# LTC7818.net
KiCad netlist of a schematic drawn in Altium Designer
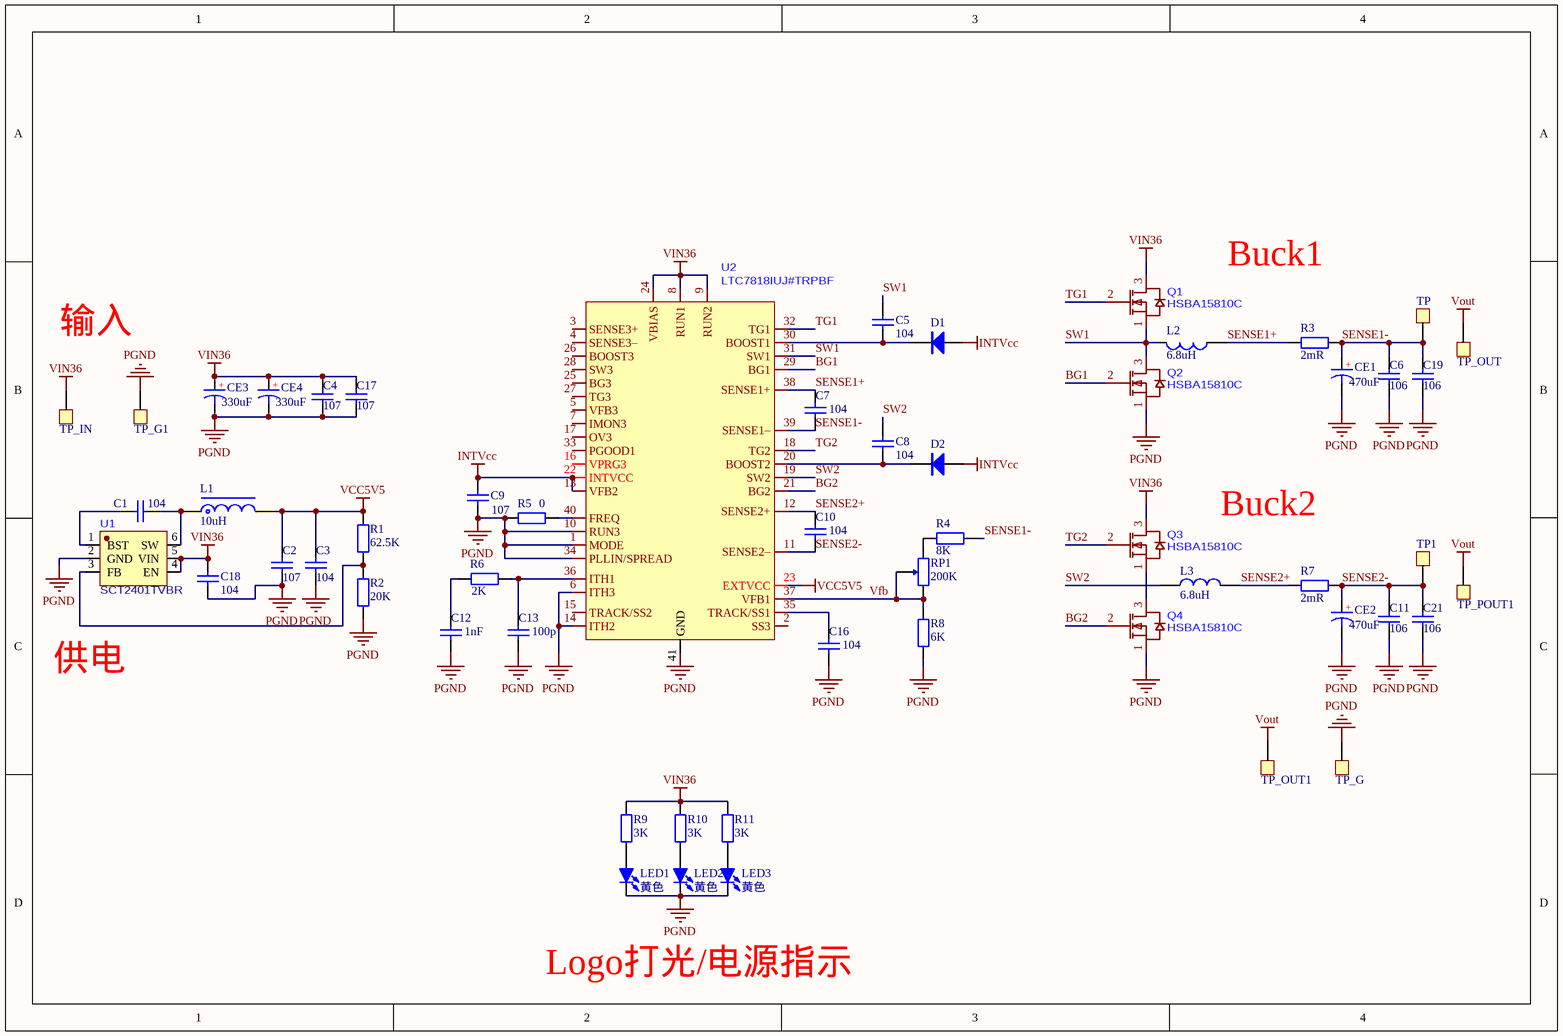
[diagram p0: LTC7818.SchDoc]

(export (version "E")
  (design (tool "Eeschema 10.0.6"))
  (components
    (comp (ref "C1")
      (value "104")
      (footprint "C0603_M")
      (description "贴片电容")
      (libsource (lib "0.1 - 电阻-电容-电感-电位器") (part "C"))
    )
    (comp (ref "C2")
      (value "107")
      (footprint "C0603_M")
      (description "贴片电容")
      (libsource (lib "0.1 - 电阻-电容-电感-电位器") (part "C"))
    )
    (comp (ref "C3")
      (value "104")
      (footprint "C0402_M")
      (description "贴片电容")
      (libsource (lib "0.1 - 电阻-电容-电感-电位器") (part "C"))
    )
    (comp (ref "C4")
      (value "107")
      (footprint "C1210_M")
      (description "贴片电容")
      (libsource (lib "0.1 - 电阻-电容-电感-电位器") (part "C"))
    )
    (comp (ref "C5")
      (value "104")
      (footprint "C0402_M")
      (description "贴片电容")
      (libsource (lib "0.1 - 电阻-电容-电感-电位器") (part "C"))
    )
    (comp (ref "C6")
      (value "106")
      (footprint "C1210_M")
      (description "贴片电容")
      (libsource (lib "0.1 - 电阻-电容-电感-电位器") (part "C"))
    )
    (comp (ref "C7")
      (value "104")
      (footprint "C0402_M")
      (description "贴片电容")
      (libsource (lib "0.1 - 电阻-电容-电感-电位器") (part "C"))
    )
    (comp (ref "C8")
      (value "104")
      (footprint "C0402_M")
      (description "贴片电容")
      (libsource (lib "0.1 - 电阻-电容-电感-电位器") (part "C"))
    )
    (comp (ref "C9")
      (value "107")
      (footprint "C0603_M")
      (description "贴片电容")
      (libsource (lib "0.1 - 电阻-电容-电感-电位器") (part "C"))
    )
    (comp (ref "C10")
      (value "104")
      (footprint "C0402_M")
      (description "贴片电容")
      (libsource (lib "0.1 - 电阻-电容-电感-电位器") (part "C"))
    )
    (comp (ref "C11")
      (value "106")
      (footprint "C1210_M")
      (description "贴片电容")
      (libsource (lib "0.1 - 电阻-电容-电感-电位器") (part "C"))
    )
    (comp (ref "C12")
      (value "1nF")
      (footprint "C0603_M")
      (description "贴片电容")
      (libsource (lib "0.1 - 电阻-电容-电感-电位器") (part "C"))
    )
    (comp (ref "C13")
      (value "100p")
      (footprint "C0603_M")
      (description "贴片电容")
      (libsource (lib "0.1 - 电阻-电容-电感-电位器") (part "C"))
    )
    (comp (ref "C16")
      (value "104")
      (footprint "C0402_M")
      (description "贴片电容")
      (libsource (lib "0.1 - 电阻-电容-电感-电位器") (part "C"))
    )
    (comp (ref "C17")
      (value "107")
      (footprint "C1210_M")
      (description "贴片电容")
      (libsource (lib "0.1 - 电阻-电容-电感-电位器") (part "C"))
    )
    (comp (ref "C18")
      (value "104")
      (footprint "C0603_M")
      (description "贴片电容")
      (libsource (lib "0.1 - 电阻-电容-电感-电位器") (part "C"))
    )
    (comp (ref "C19")
      (value "106")
      (footprint "C1210_M")
      (description "贴片电容")
      (libsource (lib "0.1 - 电阻-电容-电感-电位器") (part "C"))
    )
    (comp (ref "C21")
      (value "106")
      (footprint "C1210_M")
      (description "贴片电容")
      (libsource (lib "0.1 - 电阻-电容-电感-电位器") (part "C"))
    )
    (comp (ref "CE1")
      (value "470uF")
      (footprint "CAP 5.0*10*12.5")
      (description "直插电解电容")
      (libsource (lib "0.1 - 电阻-电容-电感-电位器") (part "CE"))
    )
    (comp (ref "CE2")
      (value "470uF")
      (footprint "CAP 5.0*10*12.5")
      (description "直插电解电容")
      (libsource (lib "0.1 - 电阻-电容-电感-电位器") (part "CE"))
    )
    (comp (ref "CE3")
      (value "330uF")
      (footprint "CAP 5.0*10*12.5")
      (description "直插电解电容")
      (libsource (lib "0.1 - 电阻-电容-电感-电位器") (part "CE"))
    )
    (comp (ref "CE4")
      (value "330uF")
      (footprint "CAP 5.0*10*12.5")
      (description "直插电解电容")
      (libsource (lib "0.1 - 电阻-电容-电感-电位器") (part "CE"))
    )
    (comp (ref "D1")
      (value "~")
      (footprint "SOD-323")
      (description "开关二极管")
      (libsource (lib "0.2 - 二极管-TVS-整流桥") (part "1N4148"))
    )
    (comp (ref "D2")
      (value "~")
      (footprint "SOD-323")
      (description "开关二极管")
      (libsource (lib "0.2 - 二极管-TVS-整流桥") (part "1N4148"))
    )
    (comp (ref "L1")
      (value "10uH")
      (footprint "L-SMD-0630")
      (description "一体成型电感")
      (libsource (lib "0.1 - 电阻-电容-电感-电位器") (part "L-Molding Choke"))
    )
    (comp (ref "L2") (value "6.8uH") (footprint "L_ SER2900") (libsource (lib "LTC7818") (part "L_ SER2900")))
    (comp (ref "L3") (value "6.8uH") (footprint "L_ SER2900") (libsource (lib "LTC7818") (part "L_ SER2900")))
    (comp (ref "LED1")
      (value "黄色")
      (footprint "LED0603_R")
      (description "贴片LED")
      (libsource (lib "0.3 - LED发光二极管") (part "LED-SMD"))
    )
    (comp (ref "LED2")
      (value "黄色")
      (footprint "LED0603_R")
      (description "贴片LED")
      (libsource (lib "0.3 - LED发光二极管") (part "LED-SMD"))
    )
    (comp (ref "LED3")
      (value "黄色")
      (footprint "LED0603_R")
      (description "贴片LED")
      (libsource (lib "0.3 - LED发光二极管") (part "LED-SMD"))
    )
    (comp (ref "Q1")
      (value "HSBA15810C")
      (footprint "PQFN-8_L6.0-W5.0-P1.27-LS6.0-BL")
      (libsource (lib "LTC7818") (part "HSBA15810C"))
    )
    (comp (ref "Q2")
      (value "HSBA15810C")
      (footprint "PQFN-8_L6.0-W5.0-P1.27-LS6.0-BL")
      (libsource (lib "LTC7818") (part "HSBA15810C"))
    )
    (comp (ref "Q3")
      (value "HSBA15810C")
      (footprint "PQFN-8_L6.0-W5.0-P1.27-LS6.0-BL")
      (libsource (lib "LTC7818") (part "HSBA15810C"))
    )
    (comp (ref "Q4")
      (value "HSBA15810C")
      (footprint "PQFN-8_L6.0-W5.0-P1.27-LS6.0-BL")
      (libsource (lib "LTC7818") (part "HSBA15810C"))
    )
    (comp (ref "R1")
      (value "62.5K")
      (footprint "R0603_M")
      (description "贴片电阻")
      (libsource (lib "0.1 - 电阻-电容-电感-电位器") (part "R"))
    )
    (comp (ref "R2")
      (value "20K")
      (footprint "R0603_M")
      (description "贴片电阻")
      (libsource (lib "0.1 - 电阻-电容-电感-电位器") (part "R"))
    )
    (comp (ref "R3")
      (value "2mR")
      (footprint "R2512_M")
      (description "贴片电阻")
      (libsource (lib "0.1 - 电阻-电容-电感-电位器") (part "R"))
    )
    (comp (ref "R4")
      (value "8K")
      (footprint "R0603_M")
      (description "贴片电阻")
      (libsource (lib "0.1 - 电阻-电容-电感-电位器") (part "R"))
    )
    (comp (ref "R5")
      (value "0")
      (footprint "R0603_M")
      (description "贴片电阻")
      (libsource (lib "0.1 - 电阻-电容-电感-电位器") (part "R"))
    )
    (comp (ref "R6")
      (value "2K")
      (footprint "R0603_M")
      (description "贴片电阻")
      (libsource (lib "0.1 - 电阻-电容-电感-电位器") (part "R"))
    )
    (comp (ref "R7")
      (value "2mR")
      (footprint "R2512_M")
      (description "贴片电阻")
      (libsource (lib "0.1 - 电阻-电容-电感-电位器") (part "R"))
    )
    (comp (ref "R8")
      (value "6K")
      (footprint "R0603_M")
      (description "贴片电阻")
      (libsource (lib "0.1 - 电阻-电容-电感-电位器") (part "R"))
    )
    (comp (ref "R9")
      (value "3K")
      (footprint "R0603_M")
      (description "贴片电阻")
      (libsource (lib "0.1 - 电阻-电容-电感-电位器") (part "R"))
    )
    (comp (ref "R10")
      (value "3K")
      (footprint "R0603_M")
      (description "贴片电阻")
      (libsource (lib "0.1 - 电阻-电容-电感-电位器") (part "R"))
    )
    (comp (ref "R11")
      (value "3K")
      (footprint "R0603_M")
      (description "贴片电阻")
      (libsource (lib "0.1 - 电阻-电容-电感-电位器") (part "R"))
    )
    (comp (ref "RP1")
      (value "200K")
      (footprint "3296W")
      (description "单联电位器")
      (libsource (lib "0.1 - 电阻-电容-电感-电位器") (part "RP"))
    )
    (comp (ref "TP") (value "TP") (footprint "CONN-TH_T44001") (libsource (lib "") (part "TP_1")))
    (comp (ref "TP1") (value "TP") (footprint "CONN-TH_T44001") (libsource (lib "") (part "TP_1")))
    (comp (ref "TP_G") (value "TP") (footprint "CONN-TH_T44001") (libsource (lib "LTC7818") (part "TP")))
    (comp (ref "TP_G1") (value "TP") (footprint "CONN-TH_T44001") (libsource (lib "LTC7818") (part "TP")))
    (comp (ref "TP_IN") (value "TP") (footprint "CONN-TH_T44001") (libsource (lib "LTC7818") (part "TP")))
    (comp (ref "TP_OUT") (value "TP") (footprint "CONN-TH_T44001") (libsource (lib "LTC7818") (part "TP")))
    (comp (ref "TP_OUT1") (value "TP") (footprint "CONN-TH_T44001") (libsource (lib "LTC7818") (part "TP")))
    (comp (ref "TP_POUT1") (value "TP") (footprint "CONN-TH_T44001") (libsource (lib "LTC7818") (part "TP")))
    (comp (ref "U1")
      (value "SCT2401TVBR")
      (footprint "SOT23-6M")
      (libsource (lib "主控板") (part "SCT2401TVBR"))
    )
    (comp (ref "U2")
      (value "LTC7818IUJ#TRPBF")
      (footprint "QFN40 6X6_M")
      (libsource (lib "LTC7818") (part "LTC7818IUJ#TRPBF"))
    )
  )
  (nets
    (net (code "1") (name "/BG1") (class "Default")
      (node (ref "Q2") (pin "2") (pinfunction "G_2") (pintype "passive"))
      (node (ref "U2") (pin "29") (pinfunction "BG1_29") (pintype "passive"))
    )
    (net (code "2") (name "/BG2") (class "Default")
      (node (ref "Q4") (pin "2") (pinfunction "G_2") (pintype "passive"))
      (node (ref "U2") (pin "21") (pinfunction "BG2_21") (pintype "passive"))
    )
    (net (code "3") (name "/SENSE1+") (class "Default")
      (node (ref "C7") (pin "1") (pinfunction "1_1") (pintype "passive"))
      (node (ref "L2") (pin "1") (pintype "power_in"))
      (node (ref "R3") (pin "1") (pinfunction "1_1") (pintype "passive"))
      (node (ref "U2") (pin "38") (pinfunction "SENSE1+_38") (pintype "passive"))
    )
    (net (code "4") (name "/SENSE1-") (class "Default")
      (node (ref "C19") (pin "2") (pinfunction "2_2") (pintype "passive"))
      (node (ref "C6") (pin "2") (pinfunction "2_2") (pintype "passive"))
      (node (ref "C7") (pin "2") (pinfunction "2_2") (pintype "passive"))
      (node (ref "CE1") (pin "1") (pinfunction "1_1") (pintype "passive"))
      (node (ref "R3") (pin "2") (pinfunction "2_2") (pintype "passive"))
      (node (ref "R4") (pin "2") (pinfunction "2_2") (pintype "passive"))
      (node (ref "TP") (pin "1") (pinfunction "1_1") (pintype "power_in"))
      (node (ref "U2") (pin "39") (pinfunction "SENSE1–_39") (pintype "passive"))
    )
    (net (code "5") (name "/SENSE2+") (class "Default")
      (node (ref "C10") (pin "1") (pinfunction "1_1") (pintype "passive"))
      (node (ref "L3") (pin "2") (pintype "power_in"))
      (node (ref "R7") (pin "1") (pinfunction "1_1") (pintype "passive"))
      (node (ref "U2") (pin "12") (pinfunction "SENSE2+_12") (pintype "passive"))
    )
    (net (code "6") (name "/SENSE2-") (class "Default")
      (node (ref "C10") (pin "2") (pinfunction "2_2") (pintype "passive"))
      (node (ref "C11") (pin "2") (pinfunction "2_2") (pintype "passive"))
      (node (ref "C21") (pin "2") (pinfunction "2_2") (pintype "passive"))
      (node (ref "CE2") (pin "1") (pinfunction "1_1") (pintype "passive"))
      (node (ref "R7") (pin "2") (pinfunction "2_2") (pintype "passive"))
      (node (ref "TP1") (pin "1") (pinfunction "1_1") (pintype "power_in"))
      (node (ref "U2") (pin "11") (pinfunction "SENSE2–_11") (pintype "passive"))
    )
    (net (code "7") (name "/SW1") (class "Default")
      (node (ref "C5") (pin "1") (pinfunction "1_1") (pintype "passive"))
      (node (ref "L2") (pin "2") (pintype "power_in"))
      (node (ref "Q1") (pin "1") (pinfunction "S_1") (pintype "passive"))
      (node (ref "Q2") (pin "3") (pinfunction "D_3") (pintype "passive"))
      (node (ref "U2") (pin "31") (pinfunction "SW1_31") (pintype "passive"))
    )
    (net (code "8") (name "/SW2") (class "Default")
      (node (ref "C8") (pin "1") (pinfunction "1_1") (pintype "passive"))
      (node (ref "L3") (pin "1") (pintype "power_in"))
      (node (ref "U2") (pin "19") (pinfunction "SW2_19") (pintype "passive"))
    )
    (net (code "9") (name "/TG1") (class "Default")
      (node (ref "Q1") (pin "2") (pinfunction "G_2") (pintype "passive"))
      (node (ref "U2") (pin "32") (pinfunction "TG1_32") (pintype "passive"))
    )
    (net (code "10") (name "/TG2") (class "Default")
      (node (ref "Q3") (pin "2") (pinfunction "G_2") (pintype "passive"))
      (node (ref "U2") (pin "18") (pinfunction "TG2_18") (pintype "passive"))
    )
    (net (code "11") (name "/Vfb") (class "Default")
      (node (ref "R8") (pin "2") (pinfunction "2_2") (pintype "passive"))
      (node (ref "RP1") (pin "1") (pinfunction "1_1") (pintype "passive"))
      (node (ref "RP1") (pin "2") (pinfunction "2_2") (pintype "passive"))
      (node (ref "U2") (pin "37") (pinfunction "VFB1_37") (pintype "passive"))
    )
    (net (code "12") (name "INTVcc") (class "Default")
      (node (ref "C9") (pin "2") (pinfunction "2_2") (pintype "passive"))
      (node (ref "D1") (pin "1") (pinfunction "A_1") (pintype "passive"))
      (node (ref "D2") (pin "1") (pinfunction "A_1") (pintype "passive"))
      (node (ref "U2") (pin "13") (pinfunction "VFB2_13") (pintype "passive"))
      (node (ref "U2") (pin "22") (pinfunction "INTVCC_22") (pintype "passive"))
    )
    (net (code "13") (name "Net-(C12-Pad1)") (class "Default")
      (node (ref "C12") (pin "1") (pinfunction "1_1") (pintype "passive"))
      (node (ref "R6") (pin "1") (pinfunction "1_1") (pintype "passive"))
    )
    (net (code "14") (name "Net-(D1-K)") (class "Default")
      (node (ref "C5") (pin "2") (pinfunction "2_2") (pintype "passive"))
      (node (ref "D1") (pin "2") (pinfunction "K_2") (pintype "passive"))
      (node (ref "U2") (pin "30") (pinfunction "BOOST1_30") (pintype "passive"))
    )
    (net (code "15") (name "Net-(D2-K)") (class "Default")
      (node (ref "C8") (pin "2") (pinfunction "2_2") (pintype "passive"))
      (node (ref "D2") (pin "2") (pinfunction "K_2") (pintype "passive"))
      (node (ref "U2") (pin "20") (pinfunction "BOOST2_20") (pintype "passive"))
    )
    (net (code "16") (name "Net-(LED1-A)") (class "Default")
      (node (ref "LED1") (pin "1") (pinfunction "A_1") (pintype "passive"))
      (node (ref "R9") (pin "1") (pinfunction "1_1") (pintype "passive"))
    )
    (net (code "17") (name "Net-(LED2-A)") (class "Default")
      (node (ref "LED2") (pin "1") (pinfunction "A_1") (pintype "passive"))
      (node (ref "R10") (pin "1") (pinfunction "1_1") (pintype "passive"))
    )
    (net (code "18") (name "Net-(LED3-A)") (class "Default")
      (node (ref "LED3") (pin "1") (pinfunction "A_1") (pintype "passive"))
      (node (ref "R11") (pin "1") (pinfunction "1_1") (pintype "passive"))
    )
    (net (code "19") (name "Net-(Q3-S)") (class "Default")
      (node (ref "Q3") (pin "1") (pinfunction "S_1") (pintype "passive"))
      (node (ref "Q4") (pin "3") (pinfunction "D_3") (pintype "passive"))
    )
    (net (code "20") (name "Net-(R4-Pad1)") (class "Default")
      (node (ref "R4") (pin "1") (pinfunction "1_1") (pintype "passive"))
      (node (ref "RP1") (pin "3") (pinfunction "3_3") (pintype "passive"))
    )
    (net (code "21") (name "Net-(U1-BST)") (class "Default")
      (node (ref "C1") (pin "1") (pinfunction "1_1") (pintype "passive"))
      (node (ref "U1") (pin "1") (pinfunction "BST_1") (pintype "passive"))
    )
    (net (code "22") (name "Net-(U1-FB)") (class "Default")
      (node (ref "R1") (pin "1") (pinfunction "1_1") (pintype "passive"))
      (node (ref "R2") (pin "2") (pinfunction "2_2") (pintype "passive"))
      (node (ref "U1") (pin "3") (pinfunction "FB_3") (pintype "passive"))
    )
    (net (code "23") (name "Net-(U1-SW)") (class "Default")
      (node (ref "C1") (pin "2") (pinfunction "2_2") (pintype "passive"))
      (node (ref "L1") (pin "1") (pinfunction "1_1") (pintype "passive"))
      (node (ref "U1") (pin "6") (pinfunction "SW_6") (pintype "passive"))
    )
    (net (code "24") (name "Net-(U2-FREQ)") (class "Default")
      (node (ref "R5") (pin "2") (pinfunction "2_2") (pintype "passive"))
      (node (ref "U2") (pin "40") (pinfunction "FREQ_40") (pintype "passive"))
    )
    (net (code "25") (name "Net-(U2-ITH1)") (class "Default")
      (node (ref "C13") (pin "1") (pinfunction "1_1") (pintype "passive"))
      (node (ref "R6") (pin "2") (pinfunction "2_2") (pintype "passive"))
      (node (ref "U2") (pin "36") (pinfunction "ITH1_36") (pintype "passive"))
    )
    (net (code "26") (name "Net-(U2-TRACK{slash}SS1)") (class "Default")
      (node (ref "C16") (pin "1") (pinfunction "1_1") (pintype "passive"))
      (node (ref "U2") (pin "35") (pinfunction "TRACK/SS1_35") (pintype "passive"))
    )
    (net (code "27") (name "PGND") (class "Default")
      (node (ref "C11") (pin "1") (pinfunction "1_1") (pintype "passive"))
      (node (ref "C12") (pin "2") (pinfunction "2_2") (pintype "passive"))
      (node (ref "C13") (pin "2") (pinfunction "2_2") (pintype "passive"))
      (node (ref "C16") (pin "2") (pinfunction "2_2") (pintype "passive"))
      (node (ref "C17") (pin "1") (pinfunction "1_1") (pintype "passive"))
      (node (ref "C18") (pin "2") (pinfunction "2_2") (pintype "passive"))
      (node (ref "C19") (pin "1") (pinfunction "1_1") (pintype "passive"))
      (node (ref "C2") (pin "2") (pinfunction "2_2") (pintype "passive"))
      (node (ref "C21") (pin "1") (pinfunction "1_1") (pintype "passive"))
      (node (ref "C3") (pin "1") (pinfunction "1_1") (pintype "passive"))
      (node (ref "C4") (pin "1") (pinfunction "1_1") (pintype "passive"))
      (node (ref "C6") (pin "1") (pinfunction "1_1") (pintype "passive"))
      (node (ref "C9") (pin "1") (pinfunction "1_1") (pintype "passive"))
      (node (ref "CE1") (pin "2") (pinfunction "2_2") (pintype "passive"))
      (node (ref "CE2") (pin "2") (pinfunction "2_2") (pintype "passive"))
      (node (ref "CE3") (pin "2") (pinfunction "2_2") (pintype "passive"))
      (node (ref "CE4") (pin "2") (pinfunction "2_2") (pintype "passive"))
      (node (ref "LED1") (pin "2") (pinfunction "K_2") (pintype "passive"))
      (node (ref "LED2") (pin "2") (pinfunction "K_2") (pintype "passive"))
      (node (ref "LED3") (pin "2") (pinfunction "K_2") (pintype "passive"))
      (node (ref "Q2") (pin "1") (pinfunction "S_1") (pintype "passive"))
      (node (ref "Q4") (pin "1") (pinfunction "S_1") (pintype "passive"))
      (node (ref "R2") (pin "1") (pinfunction "1_1") (pintype "passive"))
      (node (ref "R5") (pin "1") (pinfunction "1_1") (pintype "passive"))
      (node (ref "R8") (pin "1") (pinfunction "1_1") (pintype "passive"))
      (node (ref "TP_G") (pin "1") (pinfunction "1_1") (pintype "power_in"))
      (node (ref "TP_G1") (pin "1") (pinfunction "1_1") (pintype "power_in"))
      (node (ref "U1") (pin "2") (pinfunction "GND_2") (pintype "passive"))
      (node (ref "U2") (pin "1") (pinfunction "MODE_1") (pintype "passive"))
      (node (ref "U2") (pin "10") (pinfunction "RUN3_10") (pintype "passive"))
      (node (ref "U2") (pin "14") (pinfunction "ITH2_14") (pintype "passive"))
      (node (ref "U2") (pin "34") (pinfunction "PLLIN/SPREAD_34") (pintype "passive"))
      (node (ref "U2") (pin "41") (pinfunction "GND_41") (pintype "passive"))
      (node (ref "U2") (pin "6") (pinfunction "ITH3_6") (pintype "passive"))
    )
    (net (code "28") (name "VCC5V5") (class "Default")
      (node (ref "C2") (pin "1") (pinfunction "1_1") (pintype "passive"))
      (node (ref "C3") (pin "2") (pinfunction "2_2") (pintype "passive"))
      (node (ref "L1") (pin "2") (pinfunction "2_2") (pintype "passive"))
      (node (ref "R1") (pin "2") (pinfunction "2_2") (pintype "passive"))
      (node (ref "U2") (pin "23") (pinfunction "EXTVCC_23") (pintype "passive"))
    )
    (net (code "29") (name "VIN36") (class "Default")
      (node (ref "C17") (pin "2") (pinfunction "2_2") (pintype "passive"))
      (node (ref "C18") (pin "1") (pinfunction "1_1") (pintype "passive"))
      (node (ref "C4") (pin "2") (pinfunction "2_2") (pintype "passive"))
      (node (ref "CE3") (pin "1") (pinfunction "1_1") (pintype "passive"))
      (node (ref "CE4") (pin "1") (pinfunction "1_1") (pintype "passive"))
      (node (ref "Q1") (pin "3") (pinfunction "D_3") (pintype "passive"))
      (node (ref "Q3") (pin "3") (pinfunction "D_3") (pintype "passive"))
      (node (ref "R10") (pin "2") (pinfunction "2_2") (pintype "passive"))
      (node (ref "R11") (pin "2") (pinfunction "2_2") (pintype "passive"))
      (node (ref "R9") (pin "2") (pinfunction "2_2") (pintype "passive"))
      (node (ref "TP_IN") (pin "1") (pinfunction "1_1") (pintype "power_in"))
      (node (ref "U1") (pin "4") (pinfunction "EN_4") (pintype "passive"))
      (node (ref "U1") (pin "5") (pinfunction "VIN_5") (pintype "passive"))
      (node (ref "U2") (pin "24") (pinfunction "VBIAS_24") (pintype "passive"))
      (node (ref "U2") (pin "8") (pinfunction "RUN1_8") (pintype "passive"))
      (node (ref "U2") (pin "9") (pinfunction "RUN2_9") (pintype "passive"))
    )
    (net (code "30") (name "Vout") (class "Default")
      (node (ref "TP_OUT") (pin "1") (pinfunction "1_1") (pintype "power_in"))
      (node (ref "TP_OUT1") (pin "1") (pinfunction "1_1") (pintype "power_in"))
      (node (ref "TP_POUT1") (pin "1") (pinfunction "1_1") (pintype "power_in"))
    )
    (net (code "31") (name "unconnected-(U2-BG3-Pad25)") (class "Default")
      (node (ref "U2") (pin "25") (pinfunction "BG3_25") (pintype "passive"))
    )
    (net (code "32") (name "unconnected-(U2-BOOST3-Pad26)") (class "Default")
      (node (ref "U2") (pin "26") (pinfunction "BOOST3_26") (pintype "passive"))
    )
    (net (code "33") (name "unconnected-(U2-IMON3-Pad7)") (class "Default")
      (node (ref "U2") (pin "7") (pinfunction "IMON3_7") (pintype "passive"))
    )
    (net (code "34") (name "unconnected-(U2-OV3-Pad17)") (class "Default")
      (node (ref "U2") (pin "17") (pinfunction "OV3_17") (pintype "passive"))
    )
    (net (code "35") (name "unconnected-(U2-PGOOD1-Pad33)") (class "Default")
      (node (ref "U2") (pin "33") (pinfunction "PGOOD1_33") (pintype "passive"))
    )
    (net (code "36") (name "unconnected-(U2-SENSE3+-Pad3)") (class "Default")
      (node (ref "U2") (pin "3") (pinfunction "SENSE3+_3") (pintype "passive"))
    )
    (net (code "37") (name "unconnected-(U2-SENSE3–-Pad4)") (class "Default")
      (node (ref "U2") (pin "4") (pinfunction "SENSE3–_4") (pintype "passive"))
    )
    (net (code "38") (name "unconnected-(U2-SS3-Pad2)") (class "Default")
      (node (ref "U2") (pin "2") (pinfunction "SS3_2") (pintype "passive"))
    )
    (net (code "39") (name "unconnected-(U2-SW3-Pad28)") (class "Default")
      (node (ref "U2") (pin "28") (pinfunction "SW3_28") (pintype "passive"))
    )
    (net (code "40") (name "unconnected-(U2-TG3-Pad27)") (class "Default")
      (node (ref "U2") (pin "27") (pinfunction "TG3_27") (pintype "passive"))
    )
    (net (code "41") (name "unconnected-(U2-TRACK{slash}SS2-Pad15)") (class "Default")
      (node (ref "U2") (pin "15") (pinfunction "TRACK/SS2_15") (pintype "passive"))
    )
    (net (code "42") (name "unconnected-(U2-VFB3-Pad5)") (class "Default")
      (node (ref "U2") (pin "5") (pinfunction "VFB3_5") (pintype "passive"))
    )
    (net (code "43") (name "unconnected-(U2-VPRG3-Pad16)") (class "Default")
      (node (ref "U2") (pin "16") (pinfunction "VPRG3_16") (pintype "passive"))
    )
  )
)
